# Headlightsv1.net
KiCad netlist of a schematic drawn in EAGLE
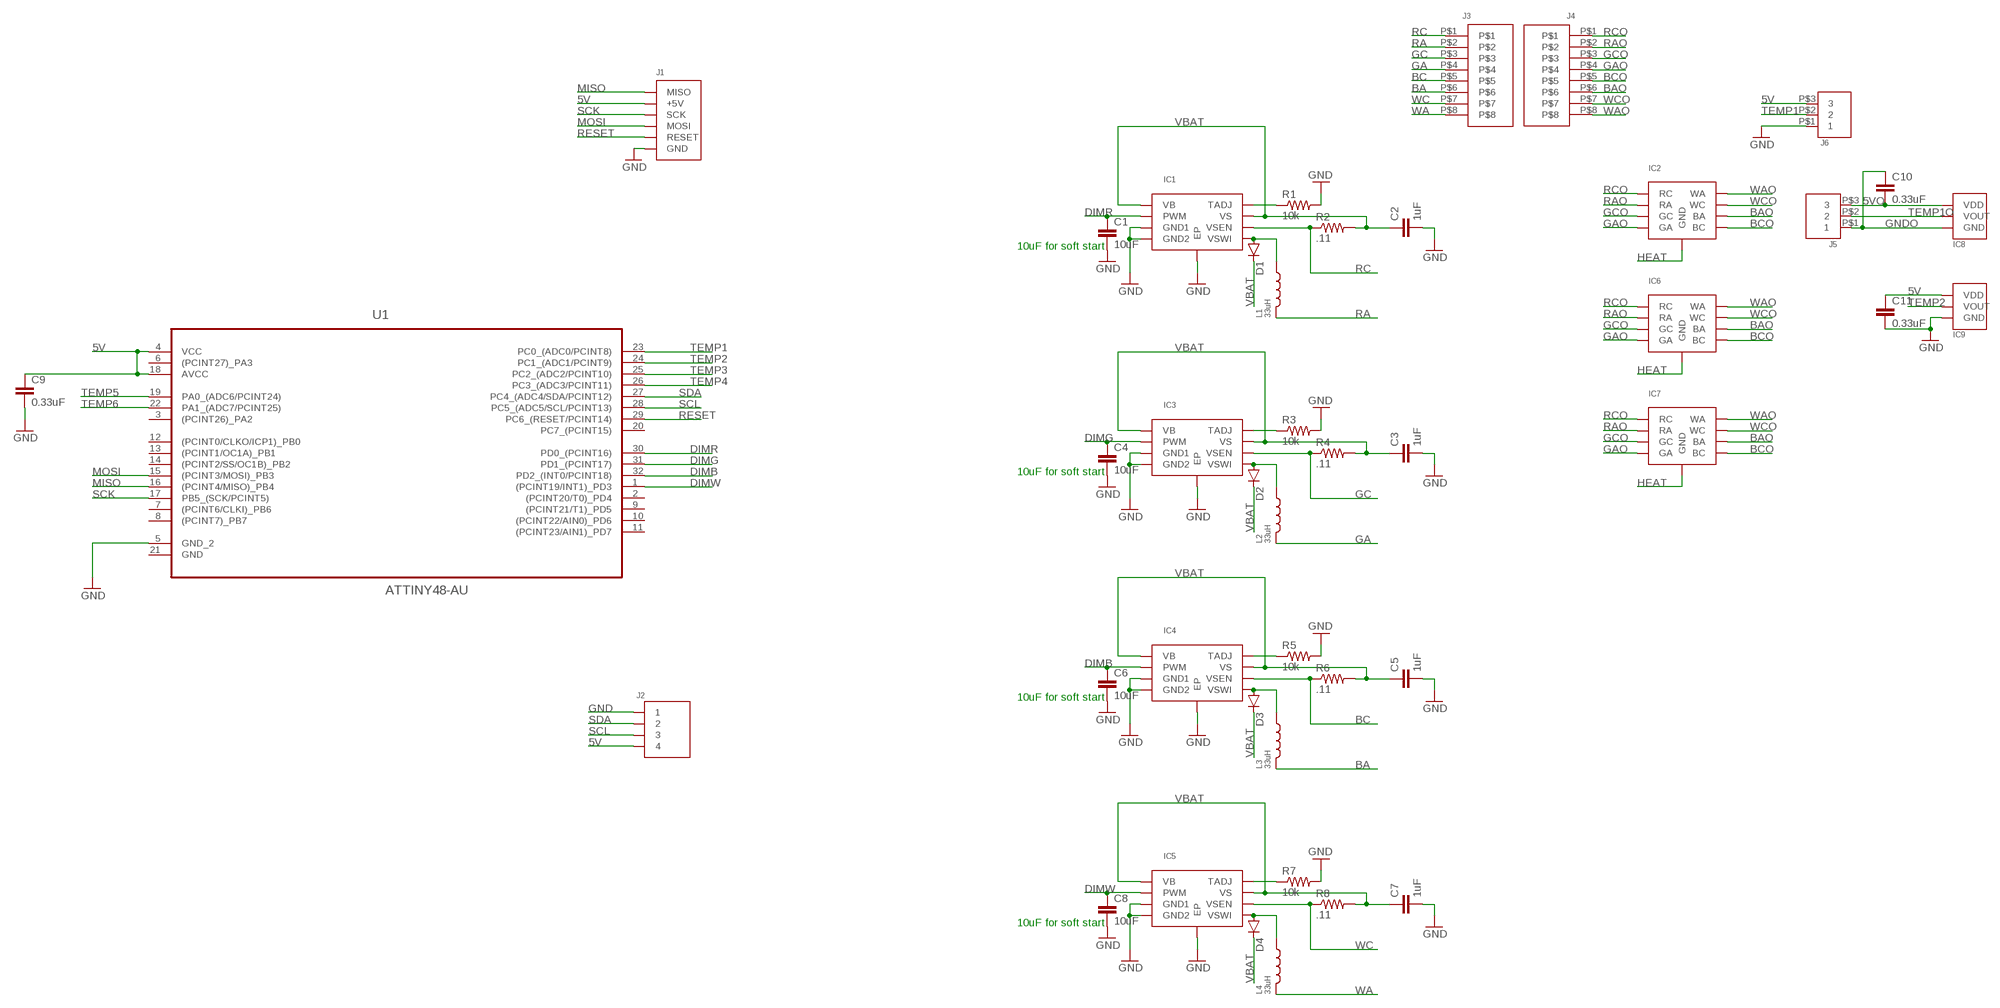
[diagram p0: schematic, sheet 1]

(export (version "E")
  (design (tool "Eeschema 10.0.6"))
  (components
    (comp (ref "C1")
      (value "10uF")
      (footprint "eagle-import:0805-CAP")
      (libsource (lib "eagle-import") (part "10UF10V10%(0805)"))
    )
    (comp (ref "C2")
      (value "1uF")
      (footprint "eagle-import:1206-CAP")
      (libsource (lib "eagle-import") (part "2.2UF50V10%(1206)"))
    )
    (comp (ref "C3")
      (value "1uF")
      (footprint "eagle-import:1206-CAP")
      (libsource (lib "eagle-import") (part "2.2UF50V10%(1206)"))
    )
    (comp (ref "C4")
      (value "10uF")
      (footprint "eagle-import:0805-CAP")
      (libsource (lib "eagle-import") (part "10UF10V10%(0805)"))
    )
    (comp (ref "C5")
      (value "1uF")
      (footprint "eagle-import:1206-CAP")
      (libsource (lib "eagle-import") (part "2.2UF50V10%(1206)"))
    )
    (comp (ref "C6")
      (value "10uF")
      (footprint "eagle-import:0805-CAP")
      (libsource (lib "eagle-import") (part "10UF10V10%(0805)"))
    )
    (comp (ref "C7")
      (value "1uF")
      (footprint "eagle-import:1206-CAP")
      (libsource (lib "eagle-import") (part "2.2UF50V10%(1206)"))
    )
    (comp (ref "C8")
      (value "10uF")
      (footprint "eagle-import:0805-CAP")
      (libsource (lib "eagle-import") (part "10UF10V10%(0805)"))
    )
    (comp (ref "C9")
      (value "0.33uF")
      (footprint "eagle-import:0805-CAP")
      (libsource (lib "eagle-import") (part "0.33UF-50V-10%(0805)"))
    )
    (comp (ref "C10")
      (value "0.33uF")
      (footprint "eagle-import:0805-CAP")
      (libsource (lib "eagle-import") (part "0.33UF-50V-10%(0805)"))
    )
    (comp (ref "C11")
      (value "0.33uF")
      (footprint "eagle-import:0805-CAP")
      (libsource (lib "eagle-import") (part "0.33UF-50V-10%(0805)"))
    )
    (comp (ref "D1")
      (value "DIODESMA-ALT")
      (footprint "eagle-import:SMA-DIODE_ALT")
      (libsource (lib "eagle-import") (part "DIODESMA-ALT"))
    )
    (comp (ref "D2")
      (value "DIODESMA-ALT")
      (footprint "eagle-import:SMA-DIODE_ALT")
      (libsource (lib "eagle-import") (part "DIODESMA-ALT"))
    )
    (comp (ref "D3")
      (value "DIODESMA-ALT")
      (footprint "eagle-import:SMA-DIODE_ALT")
      (libsource (lib "eagle-import") (part "DIODESMA-ALT"))
    )
    (comp (ref "D4")
      (value "DIODESMA-ALT")
      (footprint "eagle-import:SMA-DIODE_ALT")
      (libsource (lib "eagle-import") (part "DIODESMA-ALT"))
    )
    (comp (ref "IC1")
      (value "ILD6150_LED_DRIVER")
      (footprint "eagle-import:PG-DSO-8-27")
      (libsource (lib "eagle-import") (part "ILD6150_LED_DRIVER"))
    )
    (comp (ref "IC2")
      (value "LED_RGBW_CONF2")
      (footprint "eagle-import:LED_RGBW_CUSTOM")
      (libsource (lib "eagle-import") (part "LED_RGBW_CONF2"))
    )
    (comp (ref "IC3")
      (value "ILD6150_LED_DRIVER")
      (footprint "eagle-import:PG-DSO-8-27")
      (libsource (lib "eagle-import") (part "ILD6150_LED_DRIVER"))
    )
    (comp (ref "IC4")
      (value "ILD6150_LED_DRIVER")
      (footprint "eagle-import:PG-DSO-8-27")
      (libsource (lib "eagle-import") (part "ILD6150_LED_DRIVER"))
    )
    (comp (ref "IC5")
      (value "ILD6150_LED_DRIVER")
      (footprint "eagle-import:PG-DSO-8-27")
      (libsource (lib "eagle-import") (part "ILD6150_LED_DRIVER"))
    )
    (comp (ref "IC6")
      (value "LED_RGBW_CONF2")
      (footprint "eagle-import:LED_RGBW_CUSTOM")
      (libsource (lib "eagle-import") (part "LED_RGBW_CONF2"))
    )
    (comp (ref "IC7")
      (value "LED_RGBW_CONF2")
      (footprint "eagle-import:LED_RGBW_CUSTOM")
      (libsource (lib "eagle-import") (part "LED_RGBW_CONF2"))
    )
    (comp (ref "IC8")
      (value "TEMP_MCP9701")
      (footprint "eagle-import:SOT-23-3")
      (libsource (lib "eagle-import") (part "TEMP_MCP9701"))
    )
    (comp (ref "IC9")
      (value "TEMP_MCP9701")
      (footprint "eagle-import:SOT-23-3")
      (libsource (lib "eagle-import") (part "TEMP_MCP9701"))
    )
    (comp (ref "J1")
      (value "ISPHEADER")
      (footprint "eagle-import:2X3PIN_.1'")
      (libsource (lib "eagle-import") (part "ISPHEADER"))
    )
    (comp (ref "J2")
      (value "CONNECTOR_4PIN")
      (footprint "eagle-import:4PIN_.1'")
      (libsource (lib "eagle-import") (part "CONNECTOR_4PIN"))
    )
    (comp (ref "J3")
      (value "CONNECTOR_8PIN")
      (footprint "eagle-import:8PIN_.1'")
      (libsource (lib "eagle-import") (part "CONNECTOR_8PIN"))
    )
    (comp (ref "J4")
      (value "CONNECTOR_8PIN")
      (footprint "eagle-import:8PIN_.1'")
      (libsource (lib "eagle-import") (part "CONNECTOR_8PIN"))
    )
    (comp (ref "J5")
      (value "CONNECTOR_3PIN")
      (footprint "eagle-import:3PIN_.1'")
      (libsource (lib "eagle-import") (part "CONNECTOR_3PIN"))
    )
    (comp (ref "J6")
      (value "CONNECTOR_3PIN")
      (footprint "eagle-import:3PIN_.1'")
      (libsource (lib "eagle-import") (part "CONNECTOR_3PIN"))
    )
    (comp (ref "L1")
      (value "33uH")
      (footprint "eagle-import:IND_RLB_SERIES")
      (libsource (lib "eagle-import") (part "CHIP_IND4"))
    )
    (comp (ref "L2")
      (value "33uH")
      (footprint "eagle-import:IND_RLB_SERIES")
      (libsource (lib "eagle-import") (part "CHIP_IND4"))
    )
    (comp (ref "L3")
      (value "33uH")
      (footprint "eagle-import:IND_RLB_SERIES")
      (libsource (lib "eagle-import") (part "CHIP_IND4"))
    )
    (comp (ref "L4")
      (value "33uH")
      (footprint "eagle-import:IND_RLB_SERIES")
      (libsource (lib "eagle-import") (part "CHIP_IND4"))
    )
    (comp (ref "R1")
      (value "10k")
      (footprint "eagle-import:0805")
      (libsource (lib "eagle-import") (part "0.3OHM-1/8W-1%(0805)"))
    )
    (comp (ref "R2")
      (value ".11")
      (footprint "eagle-import:R2010")
      (libsource (lib "eagle-import") (part "0.11OHM1/2W1%(2010)"))
    )
    (comp (ref "R3")
      (value "10k")
      (footprint "eagle-import:0805")
      (libsource (lib "eagle-import") (part "0.3OHM-1/8W-1%(0805)"))
    )
    (comp (ref "R4")
      (value ".11")
      (footprint "eagle-import:R2010")
      (libsource (lib "eagle-import") (part "0.11OHM1/2W1%(2010)"))
    )
    (comp (ref "R5")
      (value "10k")
      (footprint "eagle-import:0805")
      (libsource (lib "eagle-import") (part "0.3OHM-1/8W-1%(0805)"))
    )
    (comp (ref "R6")
      (value ".11")
      (footprint "eagle-import:R2010")
      (libsource (lib "eagle-import") (part "0.11OHM1/2W1%(2010)"))
    )
    (comp (ref "R7")
      (value "10k")
      (footprint "eagle-import:0805")
      (libsource (lib "eagle-import") (part "0.3OHM-1/8W-1%(0805)"))
    )
    (comp (ref "R8")
      (value ".11")
      (footprint "eagle-import:R2010")
      (libsource (lib "eagle-import") (part "0.11OHM1/2W1%(2010)"))
    )
    (comp (ref "U1")
      (value "ATTINY48-AU")
      (footprint "eagle-import:QFP80P900X900X120-32N")
      (libsource (lib "eagle-import") (part "ATTINY48-AU"))
    )
  )
  (nets
    (net (code "1") (name "/5V") (class "Default")
      (node (ref "C11") (pin "1") (pinfunction "1_1") (pintype "passive"))
      (node (ref "C9") (pin "1") (pinfunction "1_1") (pintype "passive"))
      (node (ref "IC9") (pin "1") (pinfunction "VDD_1") (pintype "bidirectional"))
      (node (ref "J1") (pin "P$2") (pinfunction "+5V_P$2") (pintype "bidirectional"))
      (node (ref "J2") (pin "P$4") (pinfunction "4_P$4") (pintype "bidirectional"))
      (node (ref "J6") (pin "P$3") (pinfunction "3_P$3") (pintype "bidirectional"))
      (node (ref "U1") (pin "18") (pinfunction "AVCC_18") (pintype "power_in"))
      (node (ref "U1") (pin "4") (pinfunction "VCC_4") (pintype "power_in"))
    )
    (net (code "2") (name "/5VO") (class "Default")
      (node (ref "C10") (pin "2") (pinfunction "2_2") (pintype "passive"))
      (node (ref "IC8") (pin "1") (pinfunction "VDD_1") (pintype "bidirectional"))
      (node (ref "J5") (pin "P$3") (pinfunction "3_P$3") (pintype "bidirectional"))
    )
    (net (code "3") (name "/BA") (class "Default")
      (node (ref "J3") (pin "P$6") (pinfunction "P$6_P$6") (pintype "bidirectional"))
      (node (ref "L3") (pin "P$1") (pinfunction "P$1_P$1") (pintype "bidirectional"))
    )
    (net (code "4") (name "/BAO") (class "Default")
      (node (ref "IC2") (pin "6") (pinfunction "BA_6") (pintype "bidirectional"))
      (node (ref "IC6") (pin "6") (pinfunction "BA_6") (pintype "bidirectional"))
      (node (ref "IC7") (pin "6") (pinfunction "BA_6") (pintype "bidirectional"))
      (node (ref "J4") (pin "P$6") (pinfunction "P$6_P$6") (pintype "bidirectional"))
    )
    (net (code "5") (name "/BC") (class "Default")
      (node (ref "IC4") (pin "P$6") (pinfunction "VSEN_P$6") (pintype "bidirectional"))
      (node (ref "J3") (pin "P$5") (pinfunction "P$5_P$5") (pintype "bidirectional"))
      (node (ref "R6") (pin "1") (pinfunction "1_1") (pintype "passive"))
    )
    (net (code "6") (name "/BCO") (class "Default")
      (node (ref "IC2") (pin "5") (pinfunction "BC_5") (pintype "bidirectional"))
      (node (ref "IC6") (pin "5") (pinfunction "BC_5") (pintype "bidirectional"))
      (node (ref "IC7") (pin "5") (pinfunction "BC_5") (pintype "bidirectional"))
      (node (ref "J4") (pin "P$5") (pinfunction "P$5_P$5") (pintype "bidirectional"))
    )
    (net (code "7") (name "/DIMB") (class "Default")
      (node (ref "C6") (pin "1") (pinfunction "1_1") (pintype "passive"))
      (node (ref "IC4") (pin "P$2") (pinfunction "PWM_P$2") (pintype "bidirectional"))
      (node (ref "U1") (pin "32") (pinfunction "PD2_(INT0/PCINT18)_32") (pintype "bidirectional"))
    )
    (net (code "8") (name "/DIMG") (class "Default")
      (node (ref "C4") (pin "1") (pinfunction "1_1") (pintype "passive"))
      (node (ref "IC3") (pin "P$2") (pinfunction "PWM_P$2") (pintype "bidirectional"))
      (node (ref "U1") (pin "31") (pinfunction "PD1_(PCINT17)_31") (pintype "bidirectional"))
    )
    (net (code "9") (name "/DIMR") (class "Default")
      (node (ref "C1") (pin "1") (pinfunction "1_1") (pintype "passive"))
      (node (ref "IC1") (pin "P$2") (pinfunction "PWM_P$2") (pintype "bidirectional"))
      (node (ref "U1") (pin "30") (pinfunction "PD0_(PCINT16)_30") (pintype "bidirectional"))
    )
    (net (code "10") (name "/DIMW") (class "Default")
      (node (ref "C8") (pin "1") (pinfunction "1_1") (pintype "passive"))
      (node (ref "IC5") (pin "P$2") (pinfunction "PWM_P$2") (pintype "bidirectional"))
      (node (ref "U1") (pin "1") (pinfunction "(PCINT19/INT1)_PD3_1") (pintype "bidirectional"))
    )
    (net (code "11") (name "/GA") (class "Default")
      (node (ref "J3") (pin "P$4") (pinfunction "P$4_P$4") (pintype "bidirectional"))
      (node (ref "L2") (pin "P$1") (pinfunction "P$1_P$1") (pintype "bidirectional"))
    )
    (net (code "12") (name "/GAO") (class "Default")
      (node (ref "IC2") (pin "4") (pinfunction "GA_4") (pintype "bidirectional"))
      (node (ref "IC6") (pin "4") (pinfunction "GA_4") (pintype "bidirectional"))
      (node (ref "IC7") (pin "4") (pinfunction "GA_4") (pintype "bidirectional"))
      (node (ref "J4") (pin "P$4") (pinfunction "P$4_P$4") (pintype "bidirectional"))
    )
    (net (code "13") (name "/GC") (class "Default")
      (node (ref "IC3") (pin "P$6") (pinfunction "VSEN_P$6") (pintype "bidirectional"))
      (node (ref "J3") (pin "P$3") (pinfunction "P$3_P$3") (pintype "bidirectional"))
      (node (ref "R4") (pin "1") (pinfunction "1_1") (pintype "passive"))
    )
    (net (code "14") (name "/GCO") (class "Default")
      (node (ref "IC2") (pin "3") (pinfunction "GC_3") (pintype "bidirectional"))
      (node (ref "IC6") (pin "3") (pinfunction "GC_3") (pintype "bidirectional"))
      (node (ref "IC7") (pin "3") (pinfunction "GC_3") (pintype "bidirectional"))
      (node (ref "J4") (pin "P$3") (pinfunction "P$3_P$3") (pintype "bidirectional"))
    )
    (net (code "15") (name "/GNDO") (class "Default")
      (node (ref "C10") (pin "1") (pinfunction "1_1") (pintype "passive"))
      (node (ref "IC8") (pin "3") (pinfunction "GND_3") (pintype "bidirectional"))
      (node (ref "J5") (pin "P$1") (pinfunction "1_P$1") (pintype "bidirectional"))
    )
    (net (code "16") (name "/HEAT") (class "Default")
      (node (ref "IC2") (pin "9") (pinfunction "GND_9") (pintype "bidirectional"))
      (node (ref "IC6") (pin "9") (pinfunction "GND_9") (pintype "bidirectional"))
      (node (ref "IC7") (pin "9") (pinfunction "GND_9") (pintype "bidirectional"))
    )
    (net (code "17") (name "/MISO") (class "Default")
      (node (ref "J1") (pin "P$1") (pinfunction "MISO_P$1") (pintype "bidirectional"))
      (node (ref "U1") (pin "16") (pinfunction "(PCINT4/MISO)_PB4_16") (pintype "bidirectional"))
    )
    (net (code "18") (name "/MOSI") (class "Default")
      (node (ref "J1") (pin "P$4") (pinfunction "MOSI_P$4") (pintype "bidirectional"))
      (node (ref "U1") (pin "15") (pinfunction "(PCINT3/MOSI)_PB3_15") (pintype "bidirectional"))
    )
    (net (code "19") (name "/RA") (class "Default")
      (node (ref "J3") (pin "P$2") (pinfunction "P$2_P$2") (pintype "bidirectional"))
      (node (ref "L1") (pin "P$1") (pinfunction "P$1_P$1") (pintype "bidirectional"))
    )
    (net (code "20") (name "/RAO") (class "Default")
      (node (ref "IC2") (pin "2") (pinfunction "RA_2") (pintype "bidirectional"))
      (node (ref "IC6") (pin "2") (pinfunction "RA_2") (pintype "bidirectional"))
      (node (ref "IC7") (pin "2") (pinfunction "RA_2") (pintype "bidirectional"))
      (node (ref "J4") (pin "P$2") (pinfunction "P$2_P$2") (pintype "bidirectional"))
    )
    (net (code "21") (name "/RC") (class "Default")
      (node (ref "IC1") (pin "P$6") (pinfunction "VSEN_P$6") (pintype "bidirectional"))
      (node (ref "J3") (pin "P$1") (pinfunction "P$1_P$1") (pintype "bidirectional"))
      (node (ref "R2") (pin "1") (pinfunction "1_1") (pintype "passive"))
    )
    (net (code "22") (name "/RCO") (class "Default")
      (node (ref "IC2") (pin "1") (pinfunction "RC_1") (pintype "bidirectional"))
      (node (ref "IC6") (pin "1") (pinfunction "RC_1") (pintype "bidirectional"))
      (node (ref "IC7") (pin "1") (pinfunction "RC_1") (pintype "bidirectional"))
      (node (ref "J4") (pin "P$1") (pinfunction "P$1_P$1") (pintype "bidirectional"))
    )
    (net (code "23") (name "/RESET") (class "Default")
      (node (ref "J1") (pin "P$5") (pinfunction "RESET_P$5") (pintype "bidirectional"))
      (node (ref "U1") (pin "29") (pinfunction "PC6_(RESET/PCINT14)_29") (pintype "bidirectional"))
    )
    (net (code "24") (name "/SCK") (class "Default")
      (node (ref "J1") (pin "P$3") (pinfunction "SCK_P$3") (pintype "bidirectional"))
      (node (ref "U1") (pin "17") (pinfunction "PB5_(SCK/PCINT5)_17") (pintype "bidirectional"))
    )
    (net (code "25") (name "/SCL") (class "Default")
      (node (ref "J2") (pin "P$3") (pinfunction "3_P$3") (pintype "bidirectional"))
      (node (ref "U1") (pin "28") (pinfunction "PC5_(ADC5/SCL/PCINT13)_28") (pintype "bidirectional"))
    )
    (net (code "26") (name "/SDA") (class "Default")
      (node (ref "J2") (pin "P$2") (pinfunction "2_P$2") (pintype "bidirectional"))
      (node (ref "U1") (pin "27") (pinfunction "PC4_(ADC4/SDA/PCINT12)_27") (pintype "bidirectional"))
    )
    (net (code "27") (name "/TEMP1") (class "Default")
      (node (ref "J6") (pin "P$2") (pinfunction "2_P$2") (pintype "bidirectional"))
      (node (ref "U1") (pin "23") (pinfunction "PC0_(ADC0/PCINT8)_23") (pintype "bidirectional"))
    )
    (net (code "28") (name "/TEMP1O") (class "Default")
      (node (ref "IC8") (pin "2") (pinfunction "VOUT_2") (pintype "bidirectional"))
      (node (ref "J5") (pin "P$2") (pinfunction "2_P$2") (pintype "bidirectional"))
    )
    (net (code "29") (name "/TEMP2") (class "Default")
      (node (ref "IC9") (pin "2") (pinfunction "VOUT_2") (pintype "bidirectional"))
      (node (ref "U1") (pin "24") (pinfunction "PC1_(ADC1/PCINT9)_24") (pintype "bidirectional"))
    )
    (net (code "30") (name "/TEMP3") (class "Default")
      (node (ref "U1") (pin "25") (pinfunction "PC2_(ADC2/PCINT10)_25") (pintype "bidirectional"))
    )
    (net (code "31") (name "/TEMP4") (class "Default")
      (node (ref "U1") (pin "26") (pinfunction "PC3_(ADC3/PCINT11)_26") (pintype "bidirectional"))
    )
    (net (code "32") (name "/TEMP5") (class "Default")
      (node (ref "U1") (pin "19") (pinfunction "PA0_(ADC6/PCINT24)_19") (pintype "bidirectional"))
    )
    (net (code "33") (name "/TEMP6") (class "Default")
      (node (ref "U1") (pin "22") (pinfunction "PA1_(ADC7/PCINT25)_22") (pintype "bidirectional"))
    )
    (net (code "34") (name "/VBAT") (class "Default")
      (node (ref "C2") (pin "1") (pinfunction "1_1") (pintype "passive"))
      (node (ref "C3") (pin "1") (pinfunction "1_1") (pintype "passive"))
      (node (ref "C5") (pin "1") (pinfunction "1_1") (pintype "passive"))
      (node (ref "C7") (pin "1") (pinfunction "1_1") (pintype "passive"))
      (node (ref "D1") (pin "C") (pinfunction "C_C") (pintype "passive"))
      (node (ref "D2") (pin "C") (pinfunction "C_C") (pintype "passive"))
      (node (ref "D3") (pin "C") (pinfunction "C_C") (pintype "passive"))
      (node (ref "D4") (pin "C") (pinfunction "C_C") (pintype "passive"))
      (node (ref "IC1") (pin "P$1") (pinfunction "VB_P$1") (pintype "bidirectional"))
      (node (ref "IC1") (pin "P$7") (pinfunction "VS_P$7") (pintype "bidirectional"))
      (node (ref "IC3") (pin "P$1") (pinfunction "VB_P$1") (pintype "bidirectional"))
      (node (ref "IC3") (pin "P$7") (pinfunction "VS_P$7") (pintype "bidirectional"))
      (node (ref "IC4") (pin "P$1") (pinfunction "VB_P$1") (pintype "bidirectional"))
      (node (ref "IC4") (pin "P$7") (pinfunction "VS_P$7") (pintype "bidirectional"))
      (node (ref "IC5") (pin "P$1") (pinfunction "VB_P$1") (pintype "bidirectional"))
      (node (ref "IC5") (pin "P$7") (pinfunction "VS_P$7") (pintype "bidirectional"))
      (node (ref "R2") (pin "2") (pinfunction "2_2") (pintype "passive"))
      (node (ref "R4") (pin "2") (pinfunction "2_2") (pintype "passive"))
      (node (ref "R6") (pin "2") (pinfunction "2_2") (pintype "passive"))
      (node (ref "R8") (pin "2") (pinfunction "2_2") (pintype "passive"))
    )
    (net (code "35") (name "/WA") (class "Default")
      (node (ref "J3") (pin "P$8") (pinfunction "P$8_P$8") (pintype "bidirectional"))
      (node (ref "L4") (pin "P$1") (pinfunction "P$1_P$1") (pintype "bidirectional"))
    )
    (net (code "36") (name "/WAO") (class "Default")
      (node (ref "IC2") (pin "8") (pinfunction "WA_8") (pintype "bidirectional"))
      (node (ref "IC6") (pin "8") (pinfunction "WA_8") (pintype "bidirectional"))
      (node (ref "IC7") (pin "8") (pinfunction "WA_8") (pintype "bidirectional"))
      (node (ref "J4") (pin "P$8") (pinfunction "P$8_P$8") (pintype "bidirectional"))
    )
    (net (code "37") (name "/WC") (class "Default")
      (node (ref "IC5") (pin "P$6") (pinfunction "VSEN_P$6") (pintype "bidirectional"))
      (node (ref "J3") (pin "P$7") (pinfunction "P$7_P$7") (pintype "bidirectional"))
      (node (ref "R8") (pin "1") (pinfunction "1_1") (pintype "passive"))
    )
    (net (code "38") (name "/WCO") (class "Default")
      (node (ref "IC2") (pin "7") (pinfunction "WC_7") (pintype "bidirectional"))
      (node (ref "IC6") (pin "7") (pinfunction "WC_7") (pintype "bidirectional"))
      (node (ref "IC7") (pin "7") (pinfunction "WC_7") (pintype "bidirectional"))
      (node (ref "J4") (pin "P$7") (pinfunction "P$7_P$7") (pintype "bidirectional"))
    )
    (net (code "39") (name "GND") (class "Default")
      (node (ref "C1") (pin "2") (pinfunction "2_2") (pintype "passive"))
      (node (ref "C11") (pin "2") (pinfunction "2_2") (pintype "passive"))
      (node (ref "C2") (pin "2") (pinfunction "2_2") (pintype "passive"))
      (node (ref "C3") (pin "2") (pinfunction "2_2") (pintype "passive"))
      (node (ref "C4") (pin "2") (pinfunction "2_2") (pintype "passive"))
      (node (ref "C5") (pin "2") (pinfunction "2_2") (pintype "passive"))
      (node (ref "C6") (pin "2") (pinfunction "2_2") (pintype "passive"))
      (node (ref "C7") (pin "2") (pinfunction "2_2") (pintype "passive"))
      (node (ref "C8") (pin "2") (pinfunction "2_2") (pintype "passive"))
      (node (ref "C9") (pin "2") (pinfunction "2_2") (pintype "passive"))
      (node (ref "IC1") (pin "P$3") (pinfunction "GND1_P$3") (pintype "bidirectional"))
      (node (ref "IC1") (pin "P$4") (pinfunction "GND2_P$4") (pintype "bidirectional"))
      (node (ref "IC1") (pin "P$9") (pinfunction "EP_P$9") (pintype "bidirectional"))
      (node (ref "IC3") (pin "P$3") (pinfunction "GND1_P$3") (pintype "bidirectional"))
      (node (ref "IC3") (pin "P$4") (pinfunction "GND2_P$4") (pintype "bidirectional"))
      (node (ref "IC3") (pin "P$9") (pinfunction "EP_P$9") (pintype "bidirectional"))
      (node (ref "IC4") (pin "P$3") (pinfunction "GND1_P$3") (pintype "bidirectional"))
      (node (ref "IC4") (pin "P$4") (pinfunction "GND2_P$4") (pintype "bidirectional"))
      (node (ref "IC4") (pin "P$9") (pinfunction "EP_P$9") (pintype "bidirectional"))
      (node (ref "IC5") (pin "P$3") (pinfunction "GND1_P$3") (pintype "bidirectional"))
      (node (ref "IC5") (pin "P$4") (pinfunction "GND2_P$4") (pintype "bidirectional"))
      (node (ref "IC5") (pin "P$9") (pinfunction "EP_P$9") (pintype "bidirectional"))
      (node (ref "IC9") (pin "3") (pinfunction "GND_3") (pintype "bidirectional"))
      (node (ref "J1") (pin "P$6") (pinfunction "GND_P$6") (pintype "bidirectional"))
      (node (ref "J2") (pin "P$1") (pinfunction "1_P$1") (pintype "bidirectional"))
      (node (ref "J6") (pin "P$1") (pinfunction "1_P$1") (pintype "bidirectional"))
      (node (ref "R1") (pin "2") (pinfunction "2_2") (pintype "passive"))
      (node (ref "R3") (pin "2") (pinfunction "2_2") (pintype "passive"))
      (node (ref "R5") (pin "2") (pinfunction "2_2") (pintype "passive"))
      (node (ref "R7") (pin "2") (pinfunction "2_2") (pintype "passive"))
      (node (ref "U1") (pin "5") (pinfunction "GND_2_5") (pintype "passive"))
    )
    (net (code "40") (name "Net-(IC1-TADJ)") (class "Default")
      (node (ref "IC1") (pin "P$8") (pinfunction "TADJ_P$8") (pintype "bidirectional"))
      (node (ref "R1") (pin "1") (pinfunction "1_1") (pintype "passive"))
    )
    (net (code "41") (name "Net-(IC1-VSWI)") (class "Default")
      (node (ref "D1") (pin "A") (pinfunction "A_A") (pintype "passive"))
      (node (ref "IC1") (pin "P$5") (pinfunction "VSWI_P$5") (pintype "bidirectional"))
      (node (ref "L1") (pin "P$2") (pinfunction "P$2_P$2") (pintype "bidirectional"))
    )
    (net (code "42") (name "Net-(IC3-TADJ)") (class "Default")
      (node (ref "IC3") (pin "P$8") (pinfunction "TADJ_P$8") (pintype "bidirectional"))
      (node (ref "R3") (pin "1") (pinfunction "1_1") (pintype "passive"))
    )
    (net (code "43") (name "Net-(IC3-VSWI)") (class "Default")
      (node (ref "D2") (pin "A") (pinfunction "A_A") (pintype "passive"))
      (node (ref "IC3") (pin "P$5") (pinfunction "VSWI_P$5") (pintype "bidirectional"))
      (node (ref "L2") (pin "P$2") (pinfunction "P$2_P$2") (pintype "bidirectional"))
    )
    (net (code "44") (name "Net-(IC4-TADJ)") (class "Default")
      (node (ref "IC4") (pin "P$8") (pinfunction "TADJ_P$8") (pintype "bidirectional"))
      (node (ref "R5") (pin "1") (pinfunction "1_1") (pintype "passive"))
    )
    (net (code "45") (name "Net-(IC4-VSWI)") (class "Default")
      (node (ref "D3") (pin "A") (pinfunction "A_A") (pintype "passive"))
      (node (ref "IC4") (pin "P$5") (pinfunction "VSWI_P$5") (pintype "bidirectional"))
      (node (ref "L3") (pin "P$2") (pinfunction "P$2_P$2") (pintype "bidirectional"))
    )
    (net (code "46") (name "Net-(IC5-TADJ)") (class "Default")
      (node (ref "IC5") (pin "P$8") (pinfunction "TADJ_P$8") (pintype "bidirectional"))
      (node (ref "R7") (pin "1") (pinfunction "1_1") (pintype "passive"))
    )
    (net (code "47") (name "Net-(IC5-VSWI)") (class "Default")
      (node (ref "D4") (pin "A") (pinfunction "A_A") (pintype "passive"))
      (node (ref "IC5") (pin "P$5") (pinfunction "VSWI_P$5") (pintype "bidirectional"))
      (node (ref "L4") (pin "P$2") (pinfunction "P$2_P$2") (pintype "bidirectional"))
    )
    (net (code "48") (name "unconnected-(U1-(PCINT0{slash}CLKO{slash}ICP1)_PB0-Pad12)") (class "Default")
      (node (ref "U1") (pin "12") (pinfunction "(PCINT0/CLKO/ICP1)_PB0_12") (pintype "bidirectional"))
    )
    (net (code "49") (name "unconnected-(U1-(PCINT1{slash}OC1A)_PB1-Pad13)") (class "Default")
      (node (ref "U1") (pin "13") (pinfunction "(PCINT1/OC1A)_PB1_13") (pintype "bidirectional"))
    )
    (net (code "50") (name "unconnected-(U1-(PCINT2{slash}SS{slash}OC1B)_PB2-Pad14)") (class "Default")
      (node (ref "U1") (pin "14") (pinfunction "(PCINT2/SS/OC1B)_PB2_14") (pintype "bidirectional"))
    )
    (net (code "51") (name "unconnected-(U1-(PCINT6{slash}CLKI)_PB6-Pad7)") (class "Default")
      (node (ref "U1") (pin "7") (pinfunction "(PCINT6/CLKI)_PB6_7") (pintype "bidirectional"))
    )
    (net (code "52") (name "unconnected-(U1-(PCINT7)_PB7-Pad8)") (class "Default")
      (node (ref "U1") (pin "8") (pinfunction "(PCINT7)_PB7_8") (pintype "bidirectional"))
    )
    (net (code "53") (name "unconnected-(U1-(PCINT20{slash}T0)_PD4-Pad2)") (class "Default")
      (node (ref "U1") (pin "2") (pinfunction "(PCINT20/T0)_PD4_2") (pintype "bidirectional"))
    )
    (net (code "54") (name "unconnected-(U1-(PCINT21{slash}T1)_PD5-Pad9)") (class "Default")
      (node (ref "U1") (pin "9") (pinfunction "(PCINT21/T1)_PD5_9") (pintype "bidirectional"))
    )
    (net (code "55") (name "unconnected-(U1-(PCINT22{slash}AIN0)_PD6-Pad10)") (class "Default")
      (node (ref "U1") (pin "10") (pinfunction "(PCINT22/AIN0)_PD6_10") (pintype "bidirectional"))
    )
    (net (code "56") (name "unconnected-(U1-(PCINT23{slash}AIN1)_PD7-Pad11)") (class "Default")
      (node (ref "U1") (pin "11") (pinfunction "(PCINT23/AIN1)_PD7_11") (pintype "bidirectional"))
    )
    (net (code "57") (name "unconnected-(U1-(PCINT26)_PA2-Pad3)") (class "Default")
      (node (ref "U1") (pin "3") (pinfunction "(PCINT26)_PA2_3") (pintype "bidirectional"))
    )
    (net (code "58") (name "unconnected-(U1-(PCINT27)_PA3-Pad6)") (class "Default")
      (node (ref "U1") (pin "6") (pinfunction "(PCINT27)_PA3_6") (pintype "bidirectional"))
    )
    (net (code "59") (name "unconnected-(U1-GND-Pad21)") (class "Default")
      (node (ref "U1") (pin "21") (pinfunction "GND_21") (pintype "passive"))
    )
    (net (code "60") (name "unconnected-(U1-PC7_(PCINT15)-Pad20)") (class "Default")
      (node (ref "U1") (pin "20") (pinfunction "PC7_(PCINT15)_20") (pintype "bidirectional"))
    )
  )
)
